# ModCon.net
KiCad netlist of a schematic drawn in Altium Designer
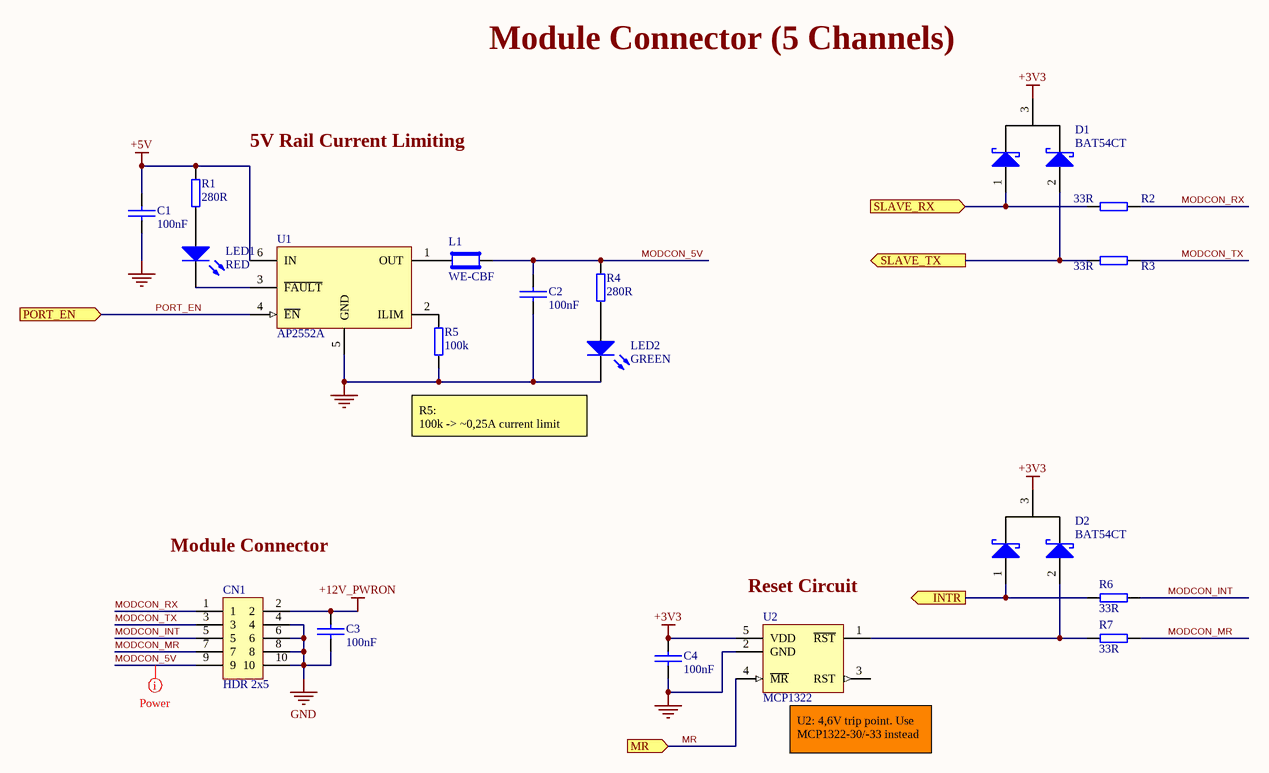
[diagram p0: ModCon.SchDoc]

(export (version "E")
  (design (tool "Eeschema 10.0.6"))
  (components
    (comp (ref "C1")
      (value "100nF")
      (footprint "C0603")
      (description "CAP CER 0.1UF 50V X7R 0603")
      (fields (field (name "PART NUMBER") "C0603C104K5RACTU") (field (name "MANUFACTURER") "Kemet"))
      (libsource (lib "AKLib") (part "CAP"))
    )
    (comp (ref "C2")
      (value "100nF")
      (footprint "C0603")
      (description "CAP CER 0.1UF 50V X7R 0603")
      (fields (field (name "PART NUMBER") "C0603C104K5RACTU") (field (name "MANUFACTURER") "Kemet"))
      (libsource (lib "AKLib") (part "CAP"))
    )
    (comp (ref "C3")
      (value "100nF")
      (footprint "C0603")
      (description "CAP CER 0.1UF 50V X7R 0603")
      (fields (field (name "PART NUMBER") "C0603C104K5RACTU") (field (name "MANUFACTURER") "Kemet"))
      (libsource (lib "AKLib") (part "CAP"))
    )
    (comp (ref "C4")
      (value "100nF")
      (footprint "C0603")
      (description "CAP CER 0.1UF 50V X7R 0603")
      (fields (field (name "PART NUMBER") "C0603C104K5RACTU") (field (name "MANUFACTURER") "Kemet"))
      (libsource (lib "AKLib") (part "CAP"))
    )
    (comp (ref "CN1")
      (value "HDR 2x5")
      (footprint "SBH11-PBPC-D05-RA-BK")
      (description "CONN HEADR 2.54MM 10POS GOLD R/A")
      (fields
        (field (name "PART NUMBER") "SBH11-PBPC-D05-RA-BK")
        (field (name "MANUFACTURER") "Sullins Connector Solutions")
      )
      (libsource (lib "AKLib") (part "Header 2x5"))
    )
    (comp (ref "D1")
      (value "BAT54CT")
      (footprint "SOT-523")
      (description "DIODE ARRAY SCHOTTKY 30V SOT523")
      (fields (field (name "PART NUMBER") "BAT54CT-7-F") (field (name "MANUFACTURER") "Diodes Incorporated"))
      (libsource (lib "AKLib") (part "Diode-Dual-CC"))
    )
    (comp (ref "D2")
      (value "BAT54CT")
      (footprint "SOT-523")
      (description "DIODE ARRAY SCHOTTKY 30V SOT523")
      (fields (field (name "PART NUMBER") "BAT54CT-7-F") (field (name "MANUFACTURER") "Diodes Incorporated"))
      (libsource (lib "AKLib") (part "Diode-Dual-CC"))
    )
    (comp (ref "L1")
      (value "WE-CBF")
      (footprint "L0603")
      (description "FERRITE BEAD 600 OHM 0603 1LN")
      (fields (field (name "PART NUMBER") "742792651") (field (name "MANUFACTURER") "Wurth Electronics Inc."))
      (libsource (lib "AKLib") (part "FBEAD"))
    )
    (comp (ref "LED1")
      (value "RED")
      (footprint "LED_0603_RED")
      (description "LED RED CLEAR 0603 SMD")
      (fields (field (name "PART NUMBER") "LTST-C190KRKT") (field (name "MANUFACTURER") "Lite-On Inc."))
      (libsource (lib "AKLib") (part "LED"))
    )
    (comp (ref "LED2")
      (value "GREEN")
      (footprint "LED_0603_GREEN")
      (description "LED GREEN CLEAR 0603 SMD")
      (fields (field (name "PART NUMBER") "LTST-C190KGKT") (field (name "MANUFACTURER") "Lite-On Inc."))
      (libsource (lib "AKLib") (part "LED"))
    )
    (comp (ref "R1")
      (value "280R")
      (footprint "R0603")
      (description "RES SMD 280 OHM 1% 1/10W 0603")
      (fields (field (name "PART NUMBER") "RC0603FR-07280RL") (field (name "MANUFACTURER") "Yageo"))
      (libsource (lib "AKLib") (part "RES"))
    )
    (comp (ref "R2")
      (value "33R")
      (footprint "R0603")
      (description "RES SMD 33 OHM 5% 1/10W 0603")
      (fields (field (name "PART NUMBER") "RC0603JR-0733RL") (field (name "MANUFACTURER") "Yageo"))
      (libsource (lib "AKLib") (part "RES"))
    )
    (comp (ref "R3")
      (value "33R")
      (footprint "R0603")
      (description "RES SMD 33 OHM 5% 1/10W 0603")
      (fields (field (name "PART NUMBER") "RC0603JR-0733RL") (field (name "MANUFACTURER") "Yageo"))
      (libsource (lib "AKLib") (part "RES"))
    )
    (comp (ref "R4")
      (value "280R")
      (footprint "R0603")
      (description "RES SMD 280 OHM 1% 1/10W 0603")
      (fields (field (name "PART NUMBER") "RC0603FR-07280RL") (field (name "MANUFACTURER") "Yageo"))
      (libsource (lib "AKLib") (part "RES"))
    )
    (comp (ref "R5")
      (value "100k")
      (footprint "R0603")
      (description "RES SMD 100K OHM 1% 1/10W 0603")
      (fields (field (name "PART NUMBER") "RC0603FR-07100KL") (field (name "MANUFACTURER") "Yageo"))
      (libsource (lib "AKLib") (part "RES"))
    )
    (comp (ref "R6")
      (value "33R")
      (footprint "R0603")
      (description "RES SMD 33 OHM 5% 1/10W 0603")
      (fields (field (name "PART NUMBER") "RC0603JR-0733RL") (field (name "MANUFACTURER") "Yageo"))
      (libsource (lib "AKLib") (part "RES"))
    )
    (comp (ref "R7")
      (value "33R")
      (footprint "R0603")
      (description "RES SMD 33 OHM 5% 1/10W 0603")
      (fields (field (name "PART NUMBER") "RC0603JR-0733RL") (field (name "MANUFACTURER") "Yageo"))
      (libsource (lib "AKLib") (part "RES"))
    )
    (comp (ref "U1")
      (value "AP2552A")
      (footprint "SOT26")
      (description "IC PD SW CURR LIMIT SOT26")
      (fields (field (name "PART NUMBER") "AP2552AW6-7") (field (name "MANUFACTURER") "Diodes Incorporated"))
      (libsource (lib "AKLib") (part "AP255xA"))
    )
    (comp (ref "U2")
      (value "MCP1322")
      (footprint "SOT23-5")
      (description "IC SUPERVISOR 4.6V SOT23-5")
      (fields
        (field (name "PART NUMBER") "MCP1322T-46LE/OT")
        (field (name "MANUFACTURER") "Microchip Technology")
      )
      (libsource (lib "AKLib") (part "MCP1322"))
    )
  )
  (nets
    (net (code "1") (name "+3V3") (class "Default")
      (node (ref "C4") (pin "2") (pinfunction "2_2") (pintype "passive"))
      (node (ref "D1") (pin "3") (pinfunction "A_3") (pintype "passive"))
      (node (ref "D2") (pin "3") (pinfunction "A_3") (pintype "passive"))
      (node (ref "U2") (pin "5") (pinfunction "VDD_5") (pintype "power_in"))
    )
    (net (code "2") (name "+5V") (class "Default")
      (node (ref "C1") (pin "2") (pinfunction "2_2") (pintype "passive"))
      (node (ref "R1") (pin "2") (pinfunction "2_2") (pintype "passive"))
      (node (ref "U1") (pin "6") (pinfunction "IN_6") (pintype "power_in"))
    )
    (net (code "3") (name "+12V_PWRON") (class "Default")
      (node (ref "C3") (pin "2") (pinfunction "2_2") (pintype "passive"))
      (node (ref "CN1") (pin "2") (pinfunction "2_2") (pintype "passive"))
    )
    (net (code "4") (name "/INTR") (class "Default")
      (node (ref "D2") (pin "1") (pinfunction "K_1") (pintype "passive"))
      (node (ref "R6") (pin "1") (pinfunction "1_1") (pintype "passive"))
    )
    (net (code "5") (name "/MODCON_5V") (class "Default")
      (node (ref "C2") (pin "2") (pinfunction "2_2") (pintype "passive"))
      (node (ref "CN1") (pin "9") (pinfunction "9_9") (pintype "passive"))
      (node (ref "L1") (pin "2") (pinfunction "2_2") (pintype "passive"))
      (node (ref "R4") (pin "2") (pinfunction "2_2") (pintype "passive"))
    )
    (net (code "6") (name "/MODCON_INT") (class "Default")
      (node (ref "CN1") (pin "5") (pinfunction "5_5") (pintype "passive"))
      (node (ref "R6") (pin "2") (pinfunction "2_2") (pintype "passive"))
    )
    (net (code "7") (name "/MODCON_MR") (class "Default")
      (node (ref "CN1") (pin "7") (pinfunction "7_7") (pintype "passive"))
      (node (ref "R7") (pin "2") (pinfunction "2_2") (pintype "passive"))
    )
    (net (code "8") (name "/MODCON_RX") (class "Default")
      (node (ref "CN1") (pin "1") (pinfunction "1_1") (pintype "passive"))
      (node (ref "R2") (pin "2") (pinfunction "2_2") (pintype "passive"))
    )
    (net (code "9") (name "/MODCON_TX") (class "Default")
      (node (ref "CN1") (pin "3") (pinfunction "3_3") (pintype "passive"))
      (node (ref "R3") (pin "2") (pinfunction "2_2") (pintype "passive"))
    )
    (net (code "10") (name "/MR") (class "Default")
      (node (ref "U2") (pin "4") (pinfunction "~{MR}_4") (pintype "input"))
    )
    (net (code "11") (name "/PORT_EN") (class "Default")
      (node (ref "U1") (pin "4") (pinfunction "~{EN}_4") (pintype "input"))
    )
    (net (code "12") (name "/SLAVE_RX") (class "Default")
      (node (ref "D1") (pin "1") (pinfunction "K_1") (pintype "passive"))
      (node (ref "R2") (pin "1") (pinfunction "1_1") (pintype "passive"))
    )
    (net (code "13") (name "/SLAVE_TX") (class "Default")
      (node (ref "D1") (pin "2") (pinfunction "K_2") (pintype "passive"))
      (node (ref "R3") (pin "1") (pinfunction "1_1") (pintype "passive"))
    )
    (net (code "14") (name "GND") (class "Default")
      (node (ref "C1") (pin "1") (pinfunction "1_1") (pintype "passive"))
      (node (ref "C2") (pin "1") (pinfunction "1_1") (pintype "passive"))
      (node (ref "C3") (pin "1") (pinfunction "1_1") (pintype "passive"))
      (node (ref "C4") (pin "1") (pinfunction "1_1") (pintype "passive"))
      (node (ref "CN1") (pin "10") (pinfunction "10_10") (pintype "passive"))
      (node (ref "CN1") (pin "4") (pinfunction "4_4") (pintype "passive"))
      (node (ref "CN1") (pin "6") (pinfunction "6_6") (pintype "passive"))
      (node (ref "CN1") (pin "8") (pinfunction "8_8") (pintype "passive"))
      (node (ref "LED2") (pin "2") (pinfunction "K_2") (pintype "passive"))
      (node (ref "R5") (pin "1") (pinfunction "1_1") (pintype "passive"))
      (node (ref "U1") (pin "5") (pinfunction "GND_5") (pintype "power_in"))
      (node (ref "U2") (pin "2") (pinfunction "GND_2") (pintype "power_in"))
    )
    (net (code "15") (name "Net-(LED1-A)") (class "Default")
      (node (ref "LED1") (pin "1") (pinfunction "A_1") (pintype "passive"))
      (node (ref "R1") (pin "1") (pinfunction "1_1") (pintype "passive"))
    )
    (net (code "16") (name "Net-(LED1-K)") (class "Default")
      (node (ref "LED1") (pin "2") (pinfunction "K_2") (pintype "passive"))
      (node (ref "U1") (pin "3") (pinfunction "~{FAULT}_3") (pintype "open_collector"))
    )
    (net (code "17") (name "Net-(LED2-A)") (class "Default")
      (node (ref "LED2") (pin "1") (pinfunction "A_1") (pintype "passive"))
      (node (ref "R4") (pin "1") (pinfunction "1_1") (pintype "passive"))
    )
    (net (code "18") (name "Net-(U1-ILIM)") (class "Default")
      (node (ref "R5") (pin "2") (pinfunction "2_2") (pintype "passive"))
      (node (ref "U1") (pin "2") (pinfunction "ILIM_2") (pintype "passive"))
    )
    (net (code "19") (name "Net-(U1-OUT)") (class "Default")
      (node (ref "L1") (pin "1") (pinfunction "1_1") (pintype "passive"))
      (node (ref "U1") (pin "1") (pinfunction "OUT_1") (pintype "power_in"))
    )
    (net (code "20") (name "Net-(U2-~{RST})") (class "Default")
      (node (ref "D2") (pin "2") (pinfunction "K_2") (pintype "passive"))
      (node (ref "R7") (pin "1") (pinfunction "1_1") (pintype "passive"))
      (node (ref "U2") (pin "1") (pinfunction "~{RST}_1") (pintype "open_collector"))
    )
    (net (code "21") (name "unconnected-(U2-RST-Pad3)") (class "Default")
      (node (ref "U2") (pin "3") (pinfunction "RST_3") (pintype "output"))
    )
  )
)
